# FUC.net
KiCad netlist of a schematic drawn in Altium Designer
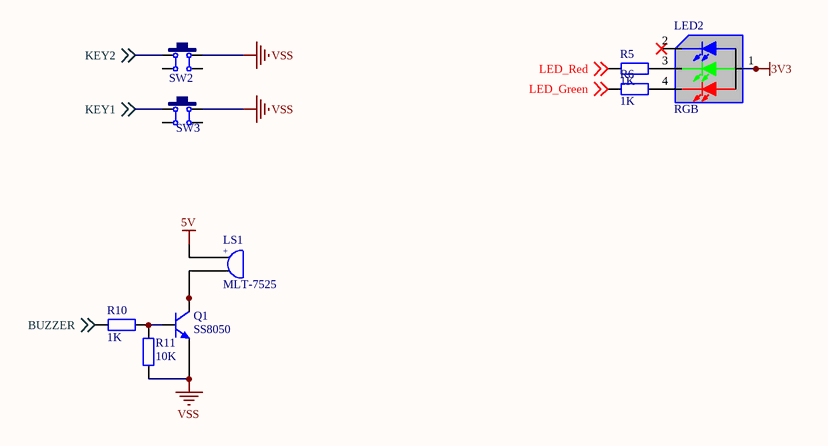
[diagram p0: FUC.SchDoc]

(export (version "E")
  (design (tool "Eeschema 10.0.6"))
  (components
    (comp (ref "LED2")
      (value "RGB")
      (footprint "LED 3528-RGB")
      (description "共阳三基色LED")
      (fields (field (name "版权归属") "源创客"))
      (libsource (lib "7.1-LED") (part "LED-RGB-A"))
    )
    (comp (ref "LS1")
      (value "MLT-7525")
      (footprint "BUZZER_7525_S")
      (description "蜂鸣器")
      (fields (field (name "版权归属") "源创客"))
      (libsource (lib "13.1-未分类器件") (part "Buzzer"))
    )
    (comp (ref "Q1")
      (value "SS8050")
      (footprint "SOT23-3L")
      (description "高频放大-NPN型")
      (fields (field (name "版权归属") "源创客"))
      (libsource (lib "5.1-三极管") (part "8050-SMD"))
    )
    (comp (ref "R5")
      (value "1K")
      (footprint "R 0603_L")
      (description "贴片电阻")
      (fields (field (name "版权归属") "源创客"))
      (libsource (lib "3.1-电阻") (part "R"))
    )
    (comp (ref "R6")
      (value "1K")
      (footprint "R 0603_L")
      (description "贴片电阻")
      (fields (field (name "版权归属") "源创客"))
      (libsource (lib "3.1-电阻") (part "R"))
    )
    (comp (ref "R10")
      (value "1K")
      (footprint "R 0603_L")
      (description "贴片电阻")
      (fields (field (name "版权归属") "源创客"))
      (libsource (lib "3.1-电阻") (part "R"))
    )
    (comp (ref "R11")
      (value "10K")
      (footprint "R 0603_L")
      (description "贴片电阻")
      (fields (field (name "版权归属") "源创客"))
      (libsource (lib "3.1-电阻") (part "R"))
    )
    (comp (ref "SW2")
      (value "3.2x4.2x2.5")
      (footprint "TSW SMD-3*4*2")
      (description "3.2x4.2轻触开关")
      (fields (field (name "版权归属") "源创客"))
      (libsource (lib "6.1-按键") (part "TSW SMD-3x4_D"))
    )
    (comp (ref "SW3")
      (value "3.2x4.2x2.5")
      (footprint "TSW SMD-3*4*2")
      (description "3.2x4.2轻触开关")
      (fields (field (name "版权归属") "源创客"))
      (libsource (lib "6.1-按键") (part "TSW SMD-3x4_D"))
    )
  )
  (nets
    (net (code "1") (name "3V3") (class "Default") (node (ref "LED2") (pin "1") (pintype "passive")))
    (net (code "2") (name "5V") (class "Default")
      (node (ref "LS1") (pin "1") (pinfunction "1_1") (pintype "passive"))
    )
    (net (code "3") (name "BUZZER") (class "Default")
      (node (ref "R10") (pin "1") (pinfunction "1_1") (pintype "passive"))
    )
    (net (code "4") (name "KEY1") (class "Default")
      (node (ref "SW3") (pin "2") (pinfunction "2_2") (pintype "passive"))
    )
    (net (code "5") (name "KEY2") (class "Default")
      (node (ref "SW2") (pin "2") (pinfunction "2_2") (pintype "passive"))
    )
    (net (code "6") (name "LED_Green") (class "Default")
      (node (ref "R6") (pin "1") (pinfunction "1_1") (pintype "passive"))
    )
    (net (code "7") (name "LED_Red") (class "Default")
      (node (ref "R5") (pin "1") (pinfunction "1_1") (pintype "passive"))
    )
    (net (code "8") (name "Net-(LED2-Pad3)") (class "Default")
      (node (ref "LED2") (pin "3") (pintype "passive"))
      (node (ref "R5") (pin "2") (pinfunction "2_2") (pintype "passive"))
    )
    (net (code "9") (name "Net-(LED2-Pad4)") (class "Default")
      (node (ref "LED2") (pin "4") (pintype "passive"))
      (node (ref "R6") (pin "2") (pinfunction "2_2") (pintype "passive"))
    )
    (net (code "10") (name "Net-(Q1-B)") (class "Default")
      (node (ref "Q1") (pin "1") (pinfunction "B_1") (pintype "passive"))
      (node (ref "R10") (pin "2") (pinfunction "2_2") (pintype "passive"))
      (node (ref "R11") (pin "1") (pinfunction "1_1") (pintype "passive"))
    )
    (net (code "11") (name "Net-(Q1-C)") (class "Default")
      (node (ref "LS1") (pin "2") (pinfunction "2_2") (pintype "passive"))
      (node (ref "Q1") (pin "3") (pinfunction "C_3") (pintype "passive"))
    )
    (net (code "12") (name "VSS") (class "Default")
      (node (ref "Q1") (pin "2") (pinfunction "E_2") (pintype "passive"))
      (node (ref "R11") (pin "2") (pinfunction "2_2") (pintype "passive"))
      (node (ref "SW2") (pin "1") (pinfunction "1_1") (pintype "passive"))
      (node (ref "SW3") (pin "1") (pinfunction "1_1") (pintype "passive"))
    )
    (net (code "13") (name "unconnected-(LED2-Pad2)") (class "Default")
      (node (ref "LED2") (pin "2") (pintype "passive+no_connect"))
    )
    (net (code "14") (name "unconnected-(SW2-Pad3)") (class "Default")
      (node (ref "SW2") (pin "3") (pinfunction "3_3") (pintype "passive"))
    )
    (net (code "15") (name "unconnected-(SW2-Pad4)") (class "Default")
      (node (ref "SW2") (pin "4") (pinfunction "4_4") (pintype "passive"))
    )
    (net (code "16") (name "unconnected-(SW3-Pad3)") (class "Default")
      (node (ref "SW3") (pin "3") (pinfunction "3_3") (pintype "passive"))
    )
    (net (code "17") (name "unconnected-(SW3-Pad4)") (class "Default")
      (node (ref "SW3") (pin "4") (pinfunction "4_4") (pintype "passive"))
    )
  )
)
